# Main.net
KiCad netlist of a schematic drawn in Altium Designer
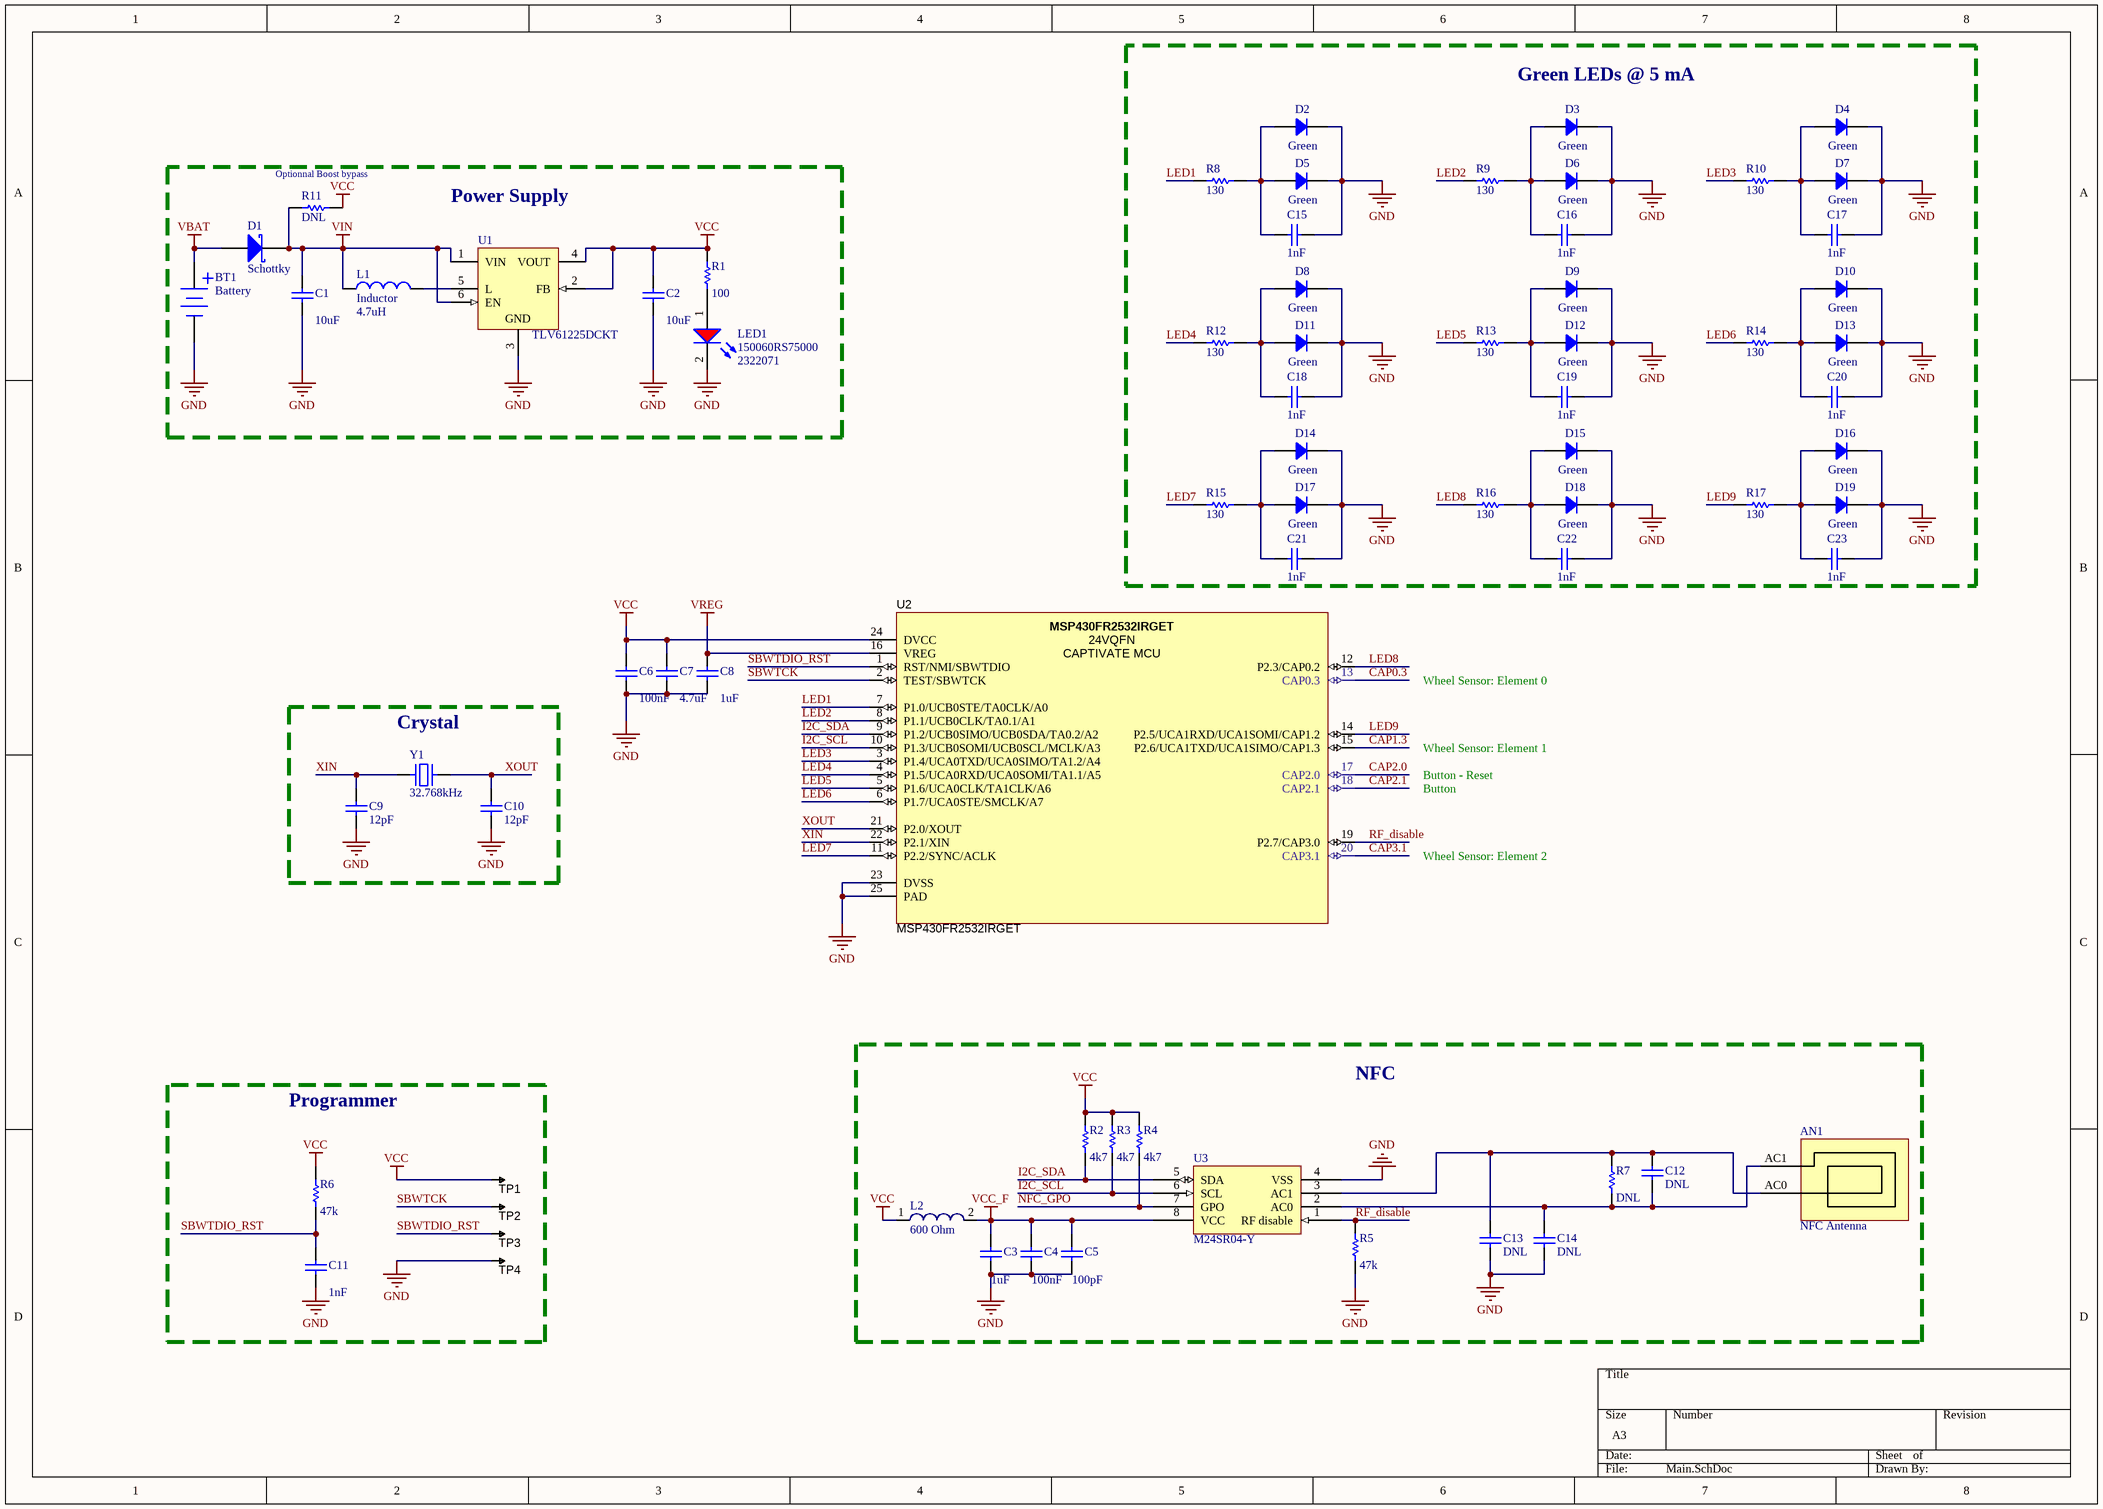
[diagram p0: Main.SchDoc]

(export (version "E")
  (design (tool "Eeschema 10.0.6"))
  (components
    (comp (ref "AN1")
      (value "NFC Antenna")
      (footprint "NFC_Antenna")
      (description "L=5.51 uH, tuned for 13.56 MHz")
      (libsource (lib "NFC_Antenna") (part "NFC_Antenna"))
    )
    (comp (ref "BT1")
      (value "Battery")
      (footprint "BC-2001")
      (description "Multicell Battery")
      (libsource (lib "BC-2001") (part "Battery"))
    )
    (comp (ref "C1")
      (value "10uF")
      (footprint "1608[0603]")
      (description "Capacitor")
      (fields (field (name "Comment") "Cap"))
      (libsource (lib "Miscellaneous Devices") (part "Cap"))
    )
    (comp (ref "C2")
      (value "10uF")
      (footprint "1608[0603]")
      (description "Capacitor")
      (fields (field (name "Comment") "Cap"))
      (libsource (lib "Miscellaneous Devices") (part "Cap"))
    )
    (comp (ref "C3")
      (value "1uF")
      (footprint "1608[0603]")
      (description "Capacitor")
      (fields (field (name "Comment") "Cap"))
      (libsource (lib "Miscellaneous Devices") (part "Cap"))
    )
    (comp (ref "C4")
      (value "100nF")
      (footprint "1608[0603]")
      (description "Capacitor")
      (fields (field (name "Comment") "Cap"))
      (libsource (lib "Miscellaneous Devices") (part "Cap"))
    )
    (comp (ref "C5")
      (value "100pF")
      (footprint "1608[0603]")
      (description "Capacitor")
      (fields (field (name "Comment") "Cap"))
      (libsource (lib "Miscellaneous Devices") (part "Cap"))
    )
    (comp (ref "C6")
      (value "100nF")
      (footprint "1608[0603]")
      (description "Capacitor")
      (fields (field (name "Comment") "Cap"))
      (libsource (lib "Miscellaneous Devices") (part "Cap"))
    )
    (comp (ref "C7")
      (value "4.7uF")
      (footprint "1608[0603]")
      (description "Capacitor")
      (fields (field (name "Comment") "Cap"))
      (libsource (lib "Miscellaneous Devices") (part "Cap"))
    )
    (comp (ref "C8")
      (value "1uF")
      (footprint "1608[0603]")
      (description "Capacitor")
      (fields (field (name "Comment") "Cap"))
      (libsource (lib "Miscellaneous Devices") (part "Cap"))
    )
    (comp (ref "C9")
      (value "12pF")
      (footprint "1608[0603]")
      (description "Capacitor")
      (fields (field (name "Comment") "Cap"))
      (libsource (lib "Miscellaneous Devices") (part "Cap"))
    )
    (comp (ref "C10")
      (value "12pF")
      (footprint "1608[0603]")
      (description "Capacitor")
      (fields (field (name "Comment") "Cap"))
      (libsource (lib "Miscellaneous Devices") (part "Cap"))
    )
    (comp (ref "C11")
      (value "1nF")
      (footprint "1608[0603]")
      (description "Capacitor")
      (fields (field (name "Comment") "Cap"))
      (libsource (lib "Miscellaneous Devices") (part "Cap"))
    )
    (comp (ref "C12")
      (value "DNL")
      (footprint "1608[0603]")
      (description "Capacitor")
      (fields (field (name "Comment") "Cap"))
      (libsource (lib "Miscellaneous Devices") (part "Cap"))
    )
    (comp (ref "C13")
      (value "DNL")
      (footprint "1608[0603]")
      (description "Capacitor")
      (fields (field (name "Comment") "Cap"))
      (libsource (lib "Miscellaneous Devices") (part "Cap"))
    )
    (comp (ref "C14")
      (value "DNL")
      (footprint "1608[0603]")
      (description "Capacitor")
      (fields (field (name "Comment") "Cap"))
      (libsource (lib "Miscellaneous Devices") (part "Cap"))
    )
    (comp (ref "C15")
      (value "1nF")
      (footprint "1608[0603]")
      (description "Capacitor")
      (fields (field (name "Comment") "Cap"))
      (libsource (lib "Miscellaneous Devices") (part "Cap"))
    )
    (comp (ref "C16")
      (value "1nF")
      (footprint "1608[0603]")
      (description "Capacitor")
      (fields (field (name "Comment") "Cap"))
      (libsource (lib "Miscellaneous Devices") (part "Cap"))
    )
    (comp (ref "C17")
      (value "1nF")
      (footprint "1608[0603]")
      (description "Capacitor")
      (fields (field (name "Comment") "Cap"))
      (libsource (lib "Miscellaneous Devices") (part "Cap"))
    )
    (comp (ref "C18")
      (value "1nF")
      (footprint "1608[0603]")
      (description "Capacitor")
      (fields (field (name "Comment") "Cap"))
      (libsource (lib "Miscellaneous Devices") (part "Cap"))
    )
    (comp (ref "C19")
      (value "1nF")
      (footprint "1608[0603]")
      (description "Capacitor")
      (fields (field (name "Comment") "Cap"))
      (libsource (lib "Miscellaneous Devices") (part "Cap"))
    )
    (comp (ref "C20")
      (value "1nF")
      (footprint "1608[0603]")
      (description "Capacitor")
      (fields (field (name "Comment") "Cap"))
      (libsource (lib "Miscellaneous Devices") (part "Cap"))
    )
    (comp (ref "C21")
      (value "1nF")
      (footprint "1608[0603]")
      (description "Capacitor")
      (fields (field (name "Comment") "Cap"))
      (libsource (lib "Miscellaneous Devices") (part "Cap"))
    )
    (comp (ref "C22")
      (value "1nF")
      (footprint "1608[0603]")
      (description "Capacitor")
      (fields (field (name "Comment") "Cap"))
      (libsource (lib "Miscellaneous Devices") (part "Cap"))
    )
    (comp (ref "C23")
      (value "1nF")
      (footprint "1608[0603]")
      (description "Capacitor")
      (fields (field (name "Comment") "Cap"))
      (libsource (lib "Miscellaneous Devices") (part "Cap"))
    )
    (comp (ref "D1")
      (value "Schottky")
      (footprint "SOT23_N")
      (description "Schottky Diode")
      (libsource (lib "Miscellaneous Devices") (part "D Schottky"))
    )
    (comp (ref "D2")
      (value "1318243")
      (footprint "LED 0805/2012 GREEN")
      (description "Rectifier Diode")
      (fields (field (name "COLOR") "Green"))
      (libsource (lib "Diodes") (part "Diode"))
    )
    (comp (ref "D3")
      (value "1318243")
      (footprint "LED 0805/2012 GREEN")
      (description "Rectifier Diode")
      (fields (field (name "COLOR") "Green"))
      (libsource (lib "Diodes") (part "Diode"))
    )
    (comp (ref "D4")
      (value "1318243")
      (footprint "LED 0805/2012 GREEN")
      (description "Rectifier Diode")
      (fields (field (name "COLOR") "Green"))
      (libsource (lib "Diodes") (part "Diode"))
    )
    (comp (ref "D5")
      (value "1318243")
      (footprint "LED 0805/2012 GREEN")
      (description "Rectifier Diode")
      (fields (field (name "COLOR") "Green"))
      (libsource (lib "Diodes") (part "Diode"))
    )
    (comp (ref "D6")
      (value "1318243")
      (footprint "LED 0805/2012 GREEN")
      (description "Rectifier Diode")
      (fields (field (name "COLOR") "Green"))
      (libsource (lib "Diodes") (part "Diode"))
    )
    (comp (ref "D7")
      (value "1318243")
      (footprint "LED 0805/2012 GREEN")
      (description "Rectifier Diode")
      (fields (field (name "COLOR") "Green"))
      (libsource (lib "Diodes") (part "Diode"))
    )
    (comp (ref "D8")
      (value "1318243")
      (footprint "LED 0805/2012 GREEN")
      (description "Rectifier Diode")
      (fields (field (name "COLOR") "Green"))
      (libsource (lib "Diodes") (part "Diode"))
    )
    (comp (ref "D9")
      (value "1318243")
      (footprint "LED 0805/2012 GREEN")
      (description "Rectifier Diode")
      (fields (field (name "COLOR") "Green"))
      (libsource (lib "Diodes") (part "Diode"))
    )
    (comp (ref "D10")
      (value "1318243")
      (footprint "LED 0805/2012 GREEN")
      (description "Rectifier Diode")
      (fields (field (name "COLOR") "Green"))
      (libsource (lib "Diodes") (part "Diode"))
    )
    (comp (ref "D11")
      (value "1318243")
      (footprint "LED 0805/2012 GREEN")
      (description "Rectifier Diode")
      (fields (field (name "COLOR") "Green"))
      (libsource (lib "Diodes") (part "Diode"))
    )
    (comp (ref "D12")
      (value "1318243")
      (footprint "LED 0805/2012 GREEN")
      (description "Rectifier Diode")
      (fields (field (name "COLOR") "Green"))
      (libsource (lib "Diodes") (part "Diode"))
    )
    (comp (ref "D13")
      (value "1318243")
      (footprint "LED 0805/2012 GREEN")
      (description "Rectifier Diode")
      (fields (field (name "COLOR") "Green"))
      (libsource (lib "Diodes") (part "Diode"))
    )
    (comp (ref "D14")
      (value "1318243")
      (footprint "LED 0805/2012 GREEN")
      (description "Rectifier Diode")
      (fields (field (name "COLOR") "Green"))
      (libsource (lib "Diodes") (part "Diode"))
    )
    (comp (ref "D15")
      (value "1318243")
      (footprint "LED 0805/2012 GREEN")
      (description "Rectifier Diode")
      (fields (field (name "COLOR") "Green"))
      (libsource (lib "Diodes") (part "Diode"))
    )
    (comp (ref "D16")
      (value "1318243")
      (footprint "LED 0805/2012 GREEN")
      (description "Rectifier Diode")
      (fields (field (name "COLOR") "Green"))
      (libsource (lib "Diodes") (part "Diode"))
    )
    (comp (ref "D17")
      (value "1318243")
      (footprint "LED 0805/2012 GREEN")
      (description "Rectifier Diode")
      (fields (field (name "COLOR") "Green"))
      (libsource (lib "Diodes") (part "Diode"))
    )
    (comp (ref "D18")
      (value "1318243")
      (footprint "LED 0805/2012 GREEN")
      (description "Rectifier Diode")
      (fields (field (name "COLOR") "Green"))
      (libsource (lib "Diodes") (part "Diode"))
    )
    (comp (ref "D19")
      (value "1318243")
      (footprint "LED 0805/2012 GREEN")
      (description "Rectifier Diode")
      (fields (field (name "COLOR") "Green"))
      (libsource (lib "Diodes") (part "Diode"))
    )
    (comp (ref "L1")
      (value "Inductor")
      (footprint "VLS2010E")
      (fields (field (name "ALTIUM_VALUE") "4.7uH"))
      (libsource (lib "Miscellaneous Devices") (part "Inductor"))
    )
    (comp (ref "L2")
      (value "600 Ohm")
      (footprint "SMD 0805")
      (description "SMD EMI Suppression Ferrite Beads WE-CBF, Z= 600 Ohm")
      (fields
        (field (name "PARTNO") "742792042")
        (field (name "MANUFACTURER") "Würth Elektronik eiSos GmbH")
        (field (name "CREATED BY") "Christin Zierenner")
      )
      (libsource (lib "WE-CBF_rev15a") (part "WE-CBF 0805, 742792042"))
    )
    (comp (ref "LED1")
      (value "150060RS75000")
      (footprint "LED_0603_Red")
      (description "SMD mono-color Chip LED, WL-SMCW, Red")
      (fields
        (field (name "MANUFACTURER") "W黵th Elektronik eiSos GmbH")
        (field (name "SUPPLIER PART NUMBER 1") "2322071")
        (field (name "CREATED BY") "Christin Otto")
      )
      (libsource (lib "WL-SMCW_rev15b") (part "WL-SMCW 0603  150060RS75000"))
    )
    (comp (ref "R1")
      (value "100")
      (footprint "J1-0603")
      (description "Resistor")
      (fields (field (name "Comment") "Res1"))
      (libsource (lib "Miscellaneous Devices") (part "Res1"))
    )
    (comp (ref "R2")
      (value "4k7")
      (footprint "J1-0603")
      (description "Resistor")
      (fields (field (name "Comment") "Res1"))
      (libsource (lib "Miscellaneous Devices") (part "Res1"))
    )
    (comp (ref "R3")
      (value "4k7")
      (footprint "J1-0603")
      (description "Resistor")
      (fields (field (name "Comment") "Res1"))
      (libsource (lib "Miscellaneous Devices") (part "Res1"))
    )
    (comp (ref "R4")
      (value "4k7")
      (footprint "J1-0603")
      (description "Resistor")
      (fields (field (name "Comment") "Res1"))
      (libsource (lib "Miscellaneous Devices") (part "Res1"))
    )
    (comp (ref "R5")
      (value "47k")
      (footprint "J1-0603")
      (description "Resistor")
      (fields (field (name "Comment") "Res1"))
      (libsource (lib "Miscellaneous Devices") (part "Res1"))
    )
    (comp (ref "R6")
      (value "47k")
      (footprint "J1-0603")
      (description "Resistor")
      (fields (field (name "Comment") "Res1"))
      (libsource (lib "Miscellaneous Devices") (part "Res1"))
    )
    (comp (ref "R7")
      (value "DNL")
      (footprint "J1-0603")
      (description "Resistor")
      (fields (field (name "Comment") "Res1"))
      (libsource (lib "Miscellaneous Devices") (part "Res1"))
    )
    (comp (ref "R8")
      (value "130")
      (footprint "J1-0603")
      (description "Resistor")
      (fields (field (name "Comment") "Res1"))
      (libsource (lib "Miscellaneous Devices") (part "Res1"))
    )
    (comp (ref "R9")
      (value "130")
      (footprint "J1-0603")
      (description "Resistor")
      (fields (field (name "Comment") "Res1"))
      (libsource (lib "Miscellaneous Devices") (part "Res1"))
    )
    (comp (ref "R10")
      (value "130")
      (footprint "J1-0603")
      (description "Resistor")
      (fields (field (name "Comment") "Res1"))
      (libsource (lib "Miscellaneous Devices") (part "Res1"))
    )
    (comp (ref "R11")
      (value "DNL")
      (footprint "J1-0603")
      (description "Resistor")
      (fields (field (name "Comment") "Res1"))
      (libsource (lib "Miscellaneous Devices") (part "Res1"))
    )
    (comp (ref "R12")
      (value "130")
      (footprint "J1-0603")
      (description "Resistor")
      (fields (field (name "Comment") "Res1"))
      (libsource (lib "Miscellaneous Devices") (part "Res1"))
    )
    (comp (ref "R13")
      (value "130")
      (footprint "J1-0603")
      (description "Resistor")
      (fields (field (name "Comment") "Res1"))
      (libsource (lib "Miscellaneous Devices") (part "Res1"))
    )
    (comp (ref "R14")
      (value "130")
      (footprint "J1-0603")
      (description "Resistor")
      (fields (field (name "Comment") "Res1"))
      (libsource (lib "Miscellaneous Devices") (part "Res1"))
    )
    (comp (ref "R15")
      (value "130")
      (footprint "J1-0603")
      (description "Resistor")
      (fields (field (name "Comment") "Res1"))
      (libsource (lib "Miscellaneous Devices") (part "Res1"))
    )
    (comp (ref "R16")
      (value "130")
      (footprint "J1-0603")
      (description "Resistor")
      (fields (field (name "Comment") "Res1"))
      (libsource (lib "Miscellaneous Devices") (part "Res1"))
    )
    (comp (ref "R17")
      (value "130")
      (footprint "J1-0603")
      (description "Resistor")
      (fields (field (name "Comment") "Res1"))
      (libsource (lib "Miscellaneous Devices") (part "Res1"))
    )
    (comp (ref "TP1")
      (value "TESTPOINT")
      (footprint "TP-R60")
      (description "SMD test pin")
      (libsource (lib "PBL - Test Points") (part "TESTPOINT"))
    )
    (comp (ref "TP2")
      (value "TESTPOINT")
      (footprint "TP-R60")
      (description "SMD test pin")
      (libsource (lib "PBL - Test Points") (part "TESTPOINT"))
    )
    (comp (ref "TP3")
      (value "TESTPOINT")
      (footprint "TP-R60")
      (description "SMD test pin")
      (libsource (lib "PBL - Test Points") (part "TESTPOINT"))
    )
    (comp (ref "TP4")
      (value "TESTPOINT")
      (footprint "TP-R60")
      (description "SMD test pin")
      (libsource (lib "PBL - Test Points") (part "TESTPOINT"))
    )
    (comp (ref "U1")
      (value "TLV61225DCKT")
      (footprint "DCK0006A_M")
      (fields (field (name "MANUFACTURER") "Texas Instruments"))
      (libsource (lib "Altium Content Vault") (part "CMP-0343-00078-2"))
    )
    (comp (ref "U2")
      (value "MSP430FR2532IRGET")
      (footprint "RGE24_N")
      (description "MSP430 Captivate Microcontroller")
      (fields (field (name "MANUFACTURER") "Texas Instruments") (field (name "SYMBOLCREATOR") "B.B."))
      (libsource (lib "MSP430FR2532") (part "MSP430FR2532IRGET"))
    )
    (comp (ref "U3")
      (value "M24SR04-Y")
      (footprint "ST TSSOP-8")
      (description "Dynamic NFC/RFID tag IC with 4-Kbit EEPROM,   NFC Forum Type 4 Tag and I²C interface")
      (libsource (lib "M24SR04-Y") (part "M24SR04-Y"))
    )
    (comp (ref "Y1")
      (value "32.768kHz")
      (footprint "ABRACON ABS25")
      (description "SMT Crystal")
      (libsource (lib "Crystals") (part "Abracon Crystal ABS25"))
    )
  )
  (nets
    (net (code "1") (name "/CAP0.3") (class "Default")
      (node (ref "U2") (pin "13") (pinfunction "CAP0.3_13") (pintype "bidirectional"))
    )
    (net (code "2") (name "/CAP1.3") (class "Default")
      (node (ref "U2") (pin "15") (pinfunction "P2.6/UCA1TXD/UCA1SIMO/CAP1.3_15") (pintype "bidirectional"))
    )
    (net (code "3") (name "/CAP2.0") (class "Default")
      (node (ref "U2") (pin "17") (pinfunction "CAP2.0_17") (pintype "bidirectional"))
    )
    (net (code "4") (name "/CAP2.1") (class "Default")
      (node (ref "U2") (pin "18") (pinfunction "CAP2.1_18") (pintype "bidirectional"))
    )
    (net (code "5") (name "/CAP3.1") (class "Default")
      (node (ref "U2") (pin "20") (pinfunction "CAP3.1_20") (pintype "bidirectional"))
    )
    (net (code "6") (name "/I2C_SCL") (class "Default")
      (node (ref "R3") (pin "1") (pinfunction "1_1") (pintype "passive"))
      (node (ref "U2") (pin "10") (pinfunction "P1.3/UCB0SOMI/UCB0SCL/MCLK/A3_10") (pintype "bidirectional"))
      (node (ref "U3") (pin "6") (pinfunction "SCL_6") (pintype "input"))
    )
    (net (code "7") (name "/I2C_SDA") (class "Default")
      (node (ref "R2") (pin "1") (pinfunction "1_1") (pintype "passive"))
      (node (ref "U2") (pin "9") (pinfunction "P1.2/UCB0SIMO/UCB0SDA/TA0.2/A2_9") (pintype "bidirectional"))
      (node (ref "U3") (pin "5") (pinfunction "SDA_5") (pintype "bidirectional"))
    )
    (net (code "8") (name "/LED1") (class "Default")
      (node (ref "R8") (pin "2") (pinfunction "2_2") (pintype "passive"))
      (node (ref "U2") (pin "7") (pinfunction "P1.0/UCB0STE/TA0CLK/A0_7") (pintype "bidirectional"))
    )
    (net (code "9") (name "/LED2") (class "Default")
      (node (ref "R9") (pin "2") (pinfunction "2_2") (pintype "passive"))
      (node (ref "U2") (pin "8") (pinfunction "P1.1/UCB0CLK/TA0.1/A1_8") (pintype "bidirectional"))
    )
    (net (code "10") (name "/LED3") (class "Default")
      (node (ref "R10") (pin "2") (pinfunction "2_2") (pintype "passive"))
      (node (ref "U2") (pin "3") (pinfunction "P1.4/UCA0TXD/UCA0SIMO/TA1.2/A4_3") (pintype "bidirectional"))
    )
    (net (code "11") (name "/LED4") (class "Default")
      (node (ref "R12") (pin "2") (pinfunction "2_2") (pintype "passive"))
      (node (ref "U2") (pin "4") (pinfunction "P1.5/UCA0RXD/UCA0SOMI/TA1.1/A5_4") (pintype "bidirectional"))
    )
    (net (code "12") (name "/LED5") (class "Default")
      (node (ref "R13") (pin "2") (pinfunction "2_2") (pintype "passive"))
      (node (ref "U2") (pin "5") (pinfunction "P1.6/UCA0CLK/TA1CLK/A6_5") (pintype "bidirectional"))
    )
    (net (code "13") (name "/LED6") (class "Default")
      (node (ref "R14") (pin "2") (pinfunction "2_2") (pintype "passive"))
      (node (ref "U2") (pin "6") (pinfunction "P1.7/UCA0STE/SMCLK/A7_6") (pintype "bidirectional"))
    )
    (net (code "14") (name "/LED7") (class "Default")
      (node (ref "R15") (pin "2") (pinfunction "2_2") (pintype "passive"))
      (node (ref "U2") (pin "11") (pinfunction "P2.2/SYNC/ACLK_11") (pintype "bidirectional"))
    )
    (net (code "15") (name "/LED8") (class "Default")
      (node (ref "R16") (pin "2") (pinfunction "2_2") (pintype "passive"))
      (node (ref "U2") (pin "12") (pinfunction "P2.3/CAP0.2_12") (pintype "bidirectional"))
    )
    (net (code "16") (name "/LED9") (class "Default")
      (node (ref "R17") (pin "2") (pinfunction "2_2") (pintype "passive"))
      (node (ref "U2") (pin "14") (pinfunction "P2.5/UCA1RXD/UCA1SOMI/CAP1.2_14") (pintype "bidirectional"))
    )
    (net (code "17") (name "/NFC_GPO") (class "Default")
      (node (ref "R4") (pin "1") (pinfunction "1_1") (pintype "passive"))
      (node (ref "U3") (pin "7") (pinfunction "GPO_7") (pintype "passive"))
    )
    (net (code "18") (name "/RF_disable") (class "Default")
      (node (ref "R5") (pin "2") (pinfunction "2_2") (pintype "passive"))
      (node (ref "U2") (pin "19") (pinfunction "P2.7/CAP3.0_19") (pintype "bidirectional"))
      (node (ref "U3") (pin "1") (pinfunction "RF_disable_1") (pintype "input"))
    )
    (net (code "19") (name "/SBWTCK") (class "Default")
      (node (ref "TP2") (pin "1") (pintype "passive"))
      (node (ref "U2") (pin "2") (pinfunction "TEST/SBWTCK_2") (pintype "bidirectional"))
    )
    (net (code "20") (name "/SBWTDIO_RST") (class "Default")
      (node (ref "C11") (pin "2") (pinfunction "2_2") (pintype "passive"))
      (node (ref "R6") (pin "1") (pinfunction "1_1") (pintype "passive"))
      (node (ref "TP3") (pin "1") (pintype "passive"))
      (node (ref "U2") (pin "1") (pinfunction "RST/NMI/SBWTDIO_1") (pintype "bidirectional"))
    )
    (net (code "21") (name "/XIN") (class "Default")
      (node (ref "C9") (pin "2") (pinfunction "2_2") (pintype "passive"))
      (node (ref "U2") (pin "22") (pinfunction "P2.1/XIN_22") (pintype "bidirectional"))
      (node (ref "Y1") (pin "1") (pinfunction "1_1") (pintype "passive"))
    )
    (net (code "22") (name "/XOUT") (class "Default")
      (node (ref "C10") (pin "2") (pinfunction "2_2") (pintype "passive"))
      (node (ref "U2") (pin "21") (pinfunction "P2.0/XOUT_21") (pintype "bidirectional"))
      (node (ref "Y1") (pin "4") (pinfunction "4_4") (pintype "passive"))
    )
    (net (code "23") (name "GND") (class "Default")
      (node (ref "BT1") (pin "2") (pinfunction "-_2") (pintype "passive"))
      (node (ref "C1") (pin "1") (pinfunction "1_1") (pintype "passive"))
      (node (ref "C10") (pin "1") (pinfunction "1_1") (pintype "passive"))
      (node (ref "C11") (pin "1") (pinfunction "1_1") (pintype "passive"))
      (node (ref "C13") (pin "1") (pinfunction "1_1") (pintype "passive"))
      (node (ref "C14") (pin "1") (pinfunction "1_1") (pintype "passive"))
      (node (ref "C15") (pin "1") (pinfunction "1_1") (pintype "passive"))
      (node (ref "C16") (pin "1") (pinfunction "1_1") (pintype "passive"))
      (node (ref "C17") (pin "1") (pinfunction "1_1") (pintype "passive"))
      (node (ref "C18") (pin "1") (pinfunction "1_1") (pintype "passive"))
      (node (ref "C19") (pin "1") (pinfunction "1_1") (pintype "passive"))
      (node (ref "C2") (pin "1") (pinfunction "1_1") (pintype "passive"))
      (node (ref "C20") (pin "1") (pinfunction "1_1") (pintype "passive"))
      (node (ref "C21") (pin "1") (pinfunction "1_1") (pintype "passive"))
      (node (ref "C22") (pin "1") (pinfunction "1_1") (pintype "passive"))
      (node (ref "C23") (pin "1") (pinfunction "1_1") (pintype "passive"))
      (node (ref "C3") (pin "1") (pinfunction "1_1") (pintype "passive"))
      (node (ref "C4") (pin "1") (pinfunction "1_1") (pintype "passive"))
      (node (ref "C5") (pin "1") (pinfunction "1_1") (pintype "passive"))
      (node (ref "C6") (pin "1") (pinfunction "1_1") (pintype "passive"))
      (node (ref "C7") (pin "1") (pinfunction "1_1") (pintype "passive"))
      (node (ref "C8") (pin "1") (pinfunction "1_1") (pintype "passive"))
      (node (ref "C9") (pin "1") (pinfunction "1_1") (pintype "passive"))
      (node (ref "D10") (pin "2") (pinfunction "2_2") (pintype "passive"))
      (node (ref "D11") (pin "2") (pinfunction "2_2") (pintype "passive"))
      (node (ref "D12") (pin "2") (pinfunction "2_2") (pintype "passive"))
      (node (ref "D13") (pin "2") (pinfunction "2_2") (pintype "passive"))
      (node (ref "D14") (pin "2") (pinfunction "2_2") (pintype "passive"))
      (node (ref "D15") (pin "2") (pinfunction "2_2") (pintype "passive"))
      (node (ref "D16") (pin "2") (pinfunction "2_2") (pintype "passive"))
      (node (ref "D17") (pin "2") (pinfunction "2_2") (pintype "passive"))
      (node (ref "D18") (pin "2") (pinfunction "2_2") (pintype "passive"))
      (node (ref "D19") (pin "2") (pinfunction "2_2") (pintype "passive"))
      (node (ref "D2") (pin "2") (pinfunction "2_2") (pintype "passive"))
      (node (ref "D3") (pin "2") (pinfunction "2_2") (pintype "passive"))
      (node (ref "D4") (pin "2") (pinfunction "2_2") (pintype "passive"))
      (node (ref "D5") (pin "2") (pinfunction "2_2") (pintype "passive"))
      (node (ref "D6") (pin "2") (pinfunction "2_2") (pintype "passive"))
      (node (ref "D7") (pin "2") (pinfunction "2_2") (pintype "passive"))
      (node (ref "D8") (pin "2") (pinfunction "2_2") (pintype "passive"))
      (node (ref "D9") (pin "2") (pinfunction "2_2") (pintype "passive"))
      (node (ref "LED1") (pin "2") (pinfunction "C_2") (pintype "passive"))
      (node (ref "R5") (pin "1") (pinfunction "1_1") (pintype "passive"))
      (node (ref "TP4") (pin "1") (pintype "passive"))
      (node (ref "U1") (pin "3") (pinfunction "GND_3") (pintype "power_in"))
      (node (ref "U2") (pin "23") (pinfunction "DVSS_23") (pintype "power_in"))
      (node (ref "U2") (pin "25") (pinfunction "PAD_25") (pintype "power_in"))
      (node (ref "U3") (pin "4") (pinfunction "VSS_4") (pintype "power_in"))
    )
    (net (code "24") (name "Net-(C15-Pad2)") (class "Default")
      (node (ref "C15") (pin "2") (pinfunction "2_2") (pintype "passive"))
      (node (ref "D2") (pin "1") (pinfunction "1_1") (pintype "passive"))
      (node (ref "D5") (pin "1") (pinfunction "1_1") (pintype "passive"))
      (node (ref "R8") (pin "1") (pinfunction "1_1") (pintype "passive"))
    )
    (net (code "25") (name "Net-(C16-Pad2)") (class "Default")
      (node (ref "C16") (pin "2") (pinfunction "2_2") (pintype "passive"))
      (node (ref "D3") (pin "1") (pinfunction "1_1") (pintype "passive"))
      (node (ref "D6") (pin "1") (pinfunction "1_1") (pintype "passive"))
      (node (ref "R9") (pin "1") (pinfunction "1_1") (pintype "passive"))
    )
    (net (code "26") (name "Net-(C17-Pad2)") (class "Default")
      (node (ref "C17") (pin "2") (pinfunction "2_2") (pintype "passive"))
      (node (ref "D4") (pin "1") (pinfunction "1_1") (pintype "passive"))
      (node (ref "D7") (pin "1") (pinfunction "1_1") (pintype "passive"))
      (node (ref "R10") (pin "1") (pinfunction "1_1") (pintype "passive"))
    )
    (net (code "27") (name "Net-(C18-Pad2)") (class "Default")
      (node (ref "C18") (pin "2") (pinfunction "2_2") (pintype "passive"))
      (node (ref "D11") (pin "1") (pinfunction "1_1") (pintype "passive"))
      (node (ref "D8") (pin "1") (pinfunction "1_1") (pintype "passive"))
      (node (ref "R12") (pin "1") (pinfunction "1_1") (pintype "passive"))
    )
    (net (code "28") (name "Net-(C19-Pad2)") (class "Default")
      (node (ref "C19") (pin "2") (pinfunction "2_2") (pintype "passive"))
      (node (ref "D12") (pin "1") (pinfunction "1_1") (pintype "passive"))
      (node (ref "D9") (pin "1") (pinfunction "1_1") (pintype "passive"))
      (node (ref "R13") (pin "1") (pinfunction "1_1") (pintype "passive"))
    )
    (net (code "29") (name "Net-(C20-Pad2)") (class "Default")
      (node (ref "C20") (pin "2") (pinfunction "2_2") (pintype "passive"))
      (node (ref "D10") (pin "1") (pinfunction "1_1") (pintype "passive"))
      (node (ref "D13") (pin "1") (pinfunction "1_1") (pintype "passive"))
      (node (ref "R14") (pin "1") (pinfunction "1_1") (pintype "passive"))
    )
    (net (code "30") (name "Net-(C21-Pad2)") (class "Default")
      (node (ref "C21") (pin "2") (pinfunction "2_2") (pintype "passive"))
      (node (ref "D14") (pin "1") (pinfunction "1_1") (pintype "passive"))
      (node (ref "D17") (pin "1") (pinfunction "1_1") (pintype "passive"))
      (node (ref "R15") (pin "1") (pinfunction "1_1") (pintype "passive"))
    )
    (net (code "31") (name "Net-(C22-Pad2)") (class "Default")
      (node (ref "C22") (pin "2") (pinfunction "2_2") (pintype "passive"))
      (node (ref "D15") (pin "1") (pinfunction "1_1") (pintype "passive"))
      (node (ref "D18") (pin "1") (pinfunction "1_1") (pintype "passive"))
      (node (ref "R16") (pin "1") (pinfunction "1_1") (pintype "passive"))
    )
    (net (code "32") (name "Net-(C23-Pad2)") (class "Default")
      (node (ref "C23") (pin "2") (pinfunction "2_2") (pintype "passive"))
      (node (ref "D16") (pin "1") (pinfunction "1_1") (pintype "passive"))
      (node (ref "D19") (pin "1") (pinfunction "1_1") (pintype "passive"))
      (node (ref "R17") (pin "1") (pinfunction "1_1") (pintype "passive"))
    )
    (net (code "33") (name "Net-(LED1-A)") (class "Default")
      (node (ref "LED1") (pin "1") (pinfunction "A_1") (pintype "passive"))
      (node (ref "R1") (pin "1") (pinfunction "1_1") (pintype "passive"))
    )
    (net (code "34") (name "Net-(U1-L)") (class "Default")
      (node (ref "L1") (pin "2") (pinfunction "2_2") (pintype "passive"))
      (node (ref "U1") (pin "5") (pinfunction "L_5") (pintype "power_in"))
    )
    (net (code "35") (name "Net-(U3-AC0)") (class "Default")
      (node (ref "AN1") (pin "AC1") (pintype "passive"))
      (node (ref "C12") (pin "1") (pinfunction "1_1") (pintype "passive"))
      (node (ref "C14") (pin "2") (pinfunction "2_2") (pintype "passive"))
      (node (ref "R7") (pin "1") (pinfunction "1_1") (pintype "passive"))
      (node (ref "U3") (pin "2") (pinfunction "AC0_2") (pintype "passive"))
    )
    (net (code "36") (name "Net-(U3-AC1)") (class "Default")
      (node (ref "AN1") (pin "AC0") (pintype "passive"))
      (node (ref "C12") (pin "2") (pinfunction "2_2") (pintype "passive"))
      (node (ref "C13") (pin "2") (pinfunction "2_2") (pintype "passive"))
      (node (ref "R7") (pin "2") (pinfunction "2_2") (pintype "passive"))
      (node (ref "U3") (pin "3") (pinfunction "AC1_3") (pintype "passive"))
    )
    (net (code "37") (name "VBAT") (class "Default")
      (node (ref "BT1") (pin "1") (pinfunction "+_1") (pintype "passive"))
      (node (ref "D1") (pin "1") (pinfunction "A_1") (pintype "passive"))
    )
    (net (code "38") (name "VCC") (class "Default")
      (node (ref "C2") (pin "2") (pinfunction "2_2") (pintype "passive"))
      (node (ref "C6") (pin "2") (pinfunction "2_2") (pintype "passive"))
      (node (ref "C7") (pin "2") (pinfunction "2_2") (pintype "passive"))
      (node (ref "L2") (pin "1") (pinfunction "1_1") (pintype "passive"))
      (node (ref "R1") (pin "2") (pinfunction "2_2") (pintype "passive"))
      (node (ref "R11") (pin "1") (pinfunction "1_1") (pintype "passive"))
      (node (ref "R2") (pin "2") (pinfunction "2_2") (pintype "passive"))
      (node (ref "R3") (pin "2") (pinfunction "2_2") (pintype "passive"))
      (node (ref "R4") (pin "2") (pinfunction "2_2") (pintype "passive"))
      (node (ref "R6") (pin "2") (pinfunction "2_2") (pintype "passive"))
      (node (ref "TP1") (pin "1") (pintype "passive"))
      (node (ref "U1") (pin "2") (pinfunction "FB_2") (pintype "input"))
      (node (ref "U1") (pin "4") (pinfunction "VOUT_4") (pintype "power_in"))
      (node (ref "U2") (pin "24") (pinfunction "DVCC_24") (pintype "power_in"))
    )
    (net (code "39") (name "VCC_F") (class "Default")
      (node (ref "C3") (pin "2") (pinfunction "2_2") (pintype "passive"))
      (node (ref "C4") (pin "2") (pinfunction "2_2") (pintype "passive"))
      (node (ref "C5") (pin "2") (pinfunction "2_2") (pintype "passive"))
      (node (ref "L2") (pin "2") (pinfunction "2_2") (pintype "passive"))
      (node (ref "U3") (pin "8") (pinfunction "VCC_8") (pintype "power_in"))
    )
    (net (code "40") (name "VIN") (class "Default")
      (node (ref "C1") (pin "2") (pinfunction "2_2") (pintype "passive"))
      (node (ref "D1") (pin "2") (pinfunction "K_2") (pintype "passive"))
      (node (ref "L1") (pin "1") (pinfunction "1_1") (pintype "passive"))
      (node (ref "R11") (pin "2") (pinfunction "2_2") (pintype "passive"))
      (node (ref "U1") (pin "1") (pinfunction "VIN_1") (pintype "power_in"))
      (node (ref "U1") (pin "6") (pinfunction "EN_6") (pintype "input"))
    )
    (net (code "41") (name "VREG") (class "Default")
      (node (ref "C8") (pin "2") (pinfunction "2_2") (pintype "passive"))
      (node (ref "U2") (pin "16") (pinfunction "VREG_16") (pintype "power_in"))
    )
  )
)
